# mesh_node.net
KiCad netlist of a schematic drawn in Altium Designer
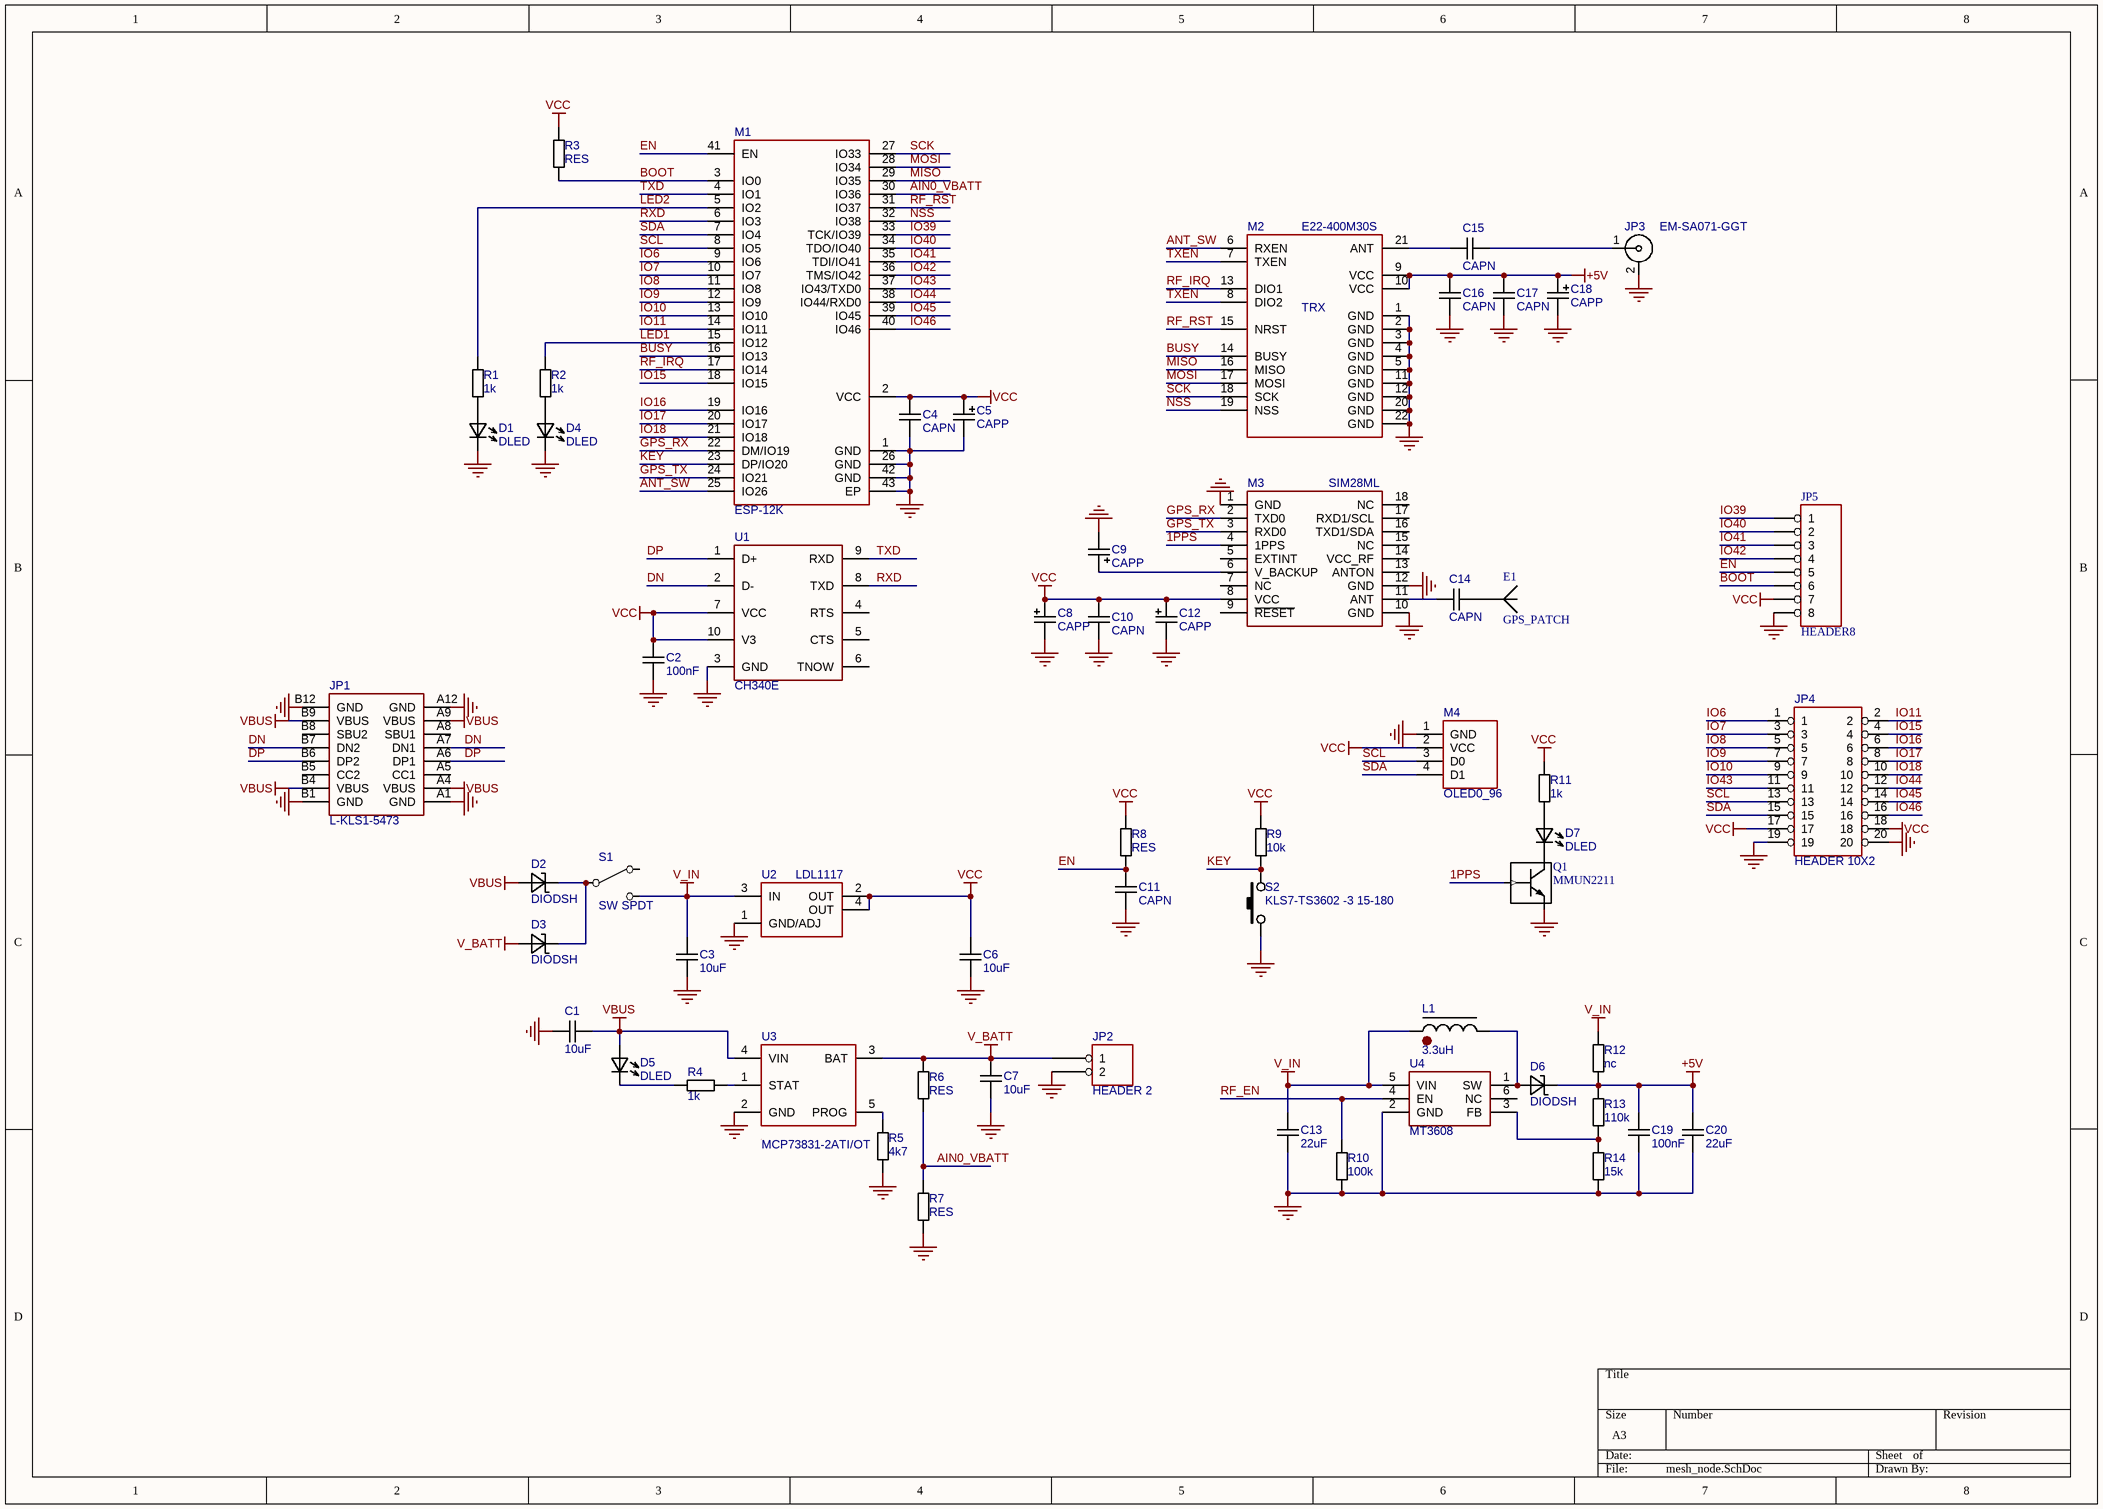
[diagram p0: mesh_node.SchDoc]

(export (version "E")
  (design (tool "Eeschema 10.0.6"))
  (components
    (comp (ref "C1")
      (value "10uF")
      (footprint "C-0805")
      (fields (field (name "VOLTAGE") "50V"))
      (libsource (lib "Passive") (part "CAPN"))
    )
    (comp (ref "C2")
      (value "100nF")
      (footprint "C-0603")
      (fields (field (name "VOLTAGE") "50V"))
      (libsource (lib "Passive") (part "CAPN"))
    )
    (comp (ref "C3")
      (value "10uF")
      (footprint "C-0805")
      (fields (field (name "VOLTAGE") "50V"))
      (libsource (lib "Passive") (part "CAPN"))
    )
    (comp (ref "C4")
      (value "CAPN")
      (footprint "C-0603")
      (fields (field (name "VOLTAGE") "50V"))
      (libsource (lib "Passive") (part "CAPN"))
    )
    (comp (ref "C5")
      (value "CAPP")
      (footprint "C_TANTAL_C")
      (fields (field (name "VOLTAGE") "16V"))
      (libsource (lib "Passive") (part "CAPP"))
    )
    (comp (ref "C6")
      (value "10uF")
      (footprint "C-0805")
      (fields (field (name "VOLTAGE") "50V"))
      (libsource (lib "Passive") (part "CAPN"))
    )
    (comp (ref "C7")
      (value "10uF")
      (footprint "C-0805")
      (fields (field (name "VOLTAGE") "50V"))
      (libsource (lib "Passive") (part "CAPN"))
    )
    (comp (ref "C8")
      (value "CAPP")
      (footprint "C_TANTAL_C")
      (fields (field (name "VOLTAGE") "16V"))
      (libsource (lib "Passive") (part "CAPP"))
    )
    (comp (ref "C9")
      (value "CAPP")
      (footprint "C_TANTAL_C")
      (fields (field (name "VOLTAGE") "16V"))
      (libsource (lib "Passive") (part "CAPP"))
    )
    (comp (ref "C10")
      (value "CAPN")
      (footprint "C-0603")
      (fields (field (name "VOLTAGE") "50V"))
      (libsource (lib "Passive") (part "CAPN"))
    )
    (comp (ref "C11")
      (value "CAPN")
      (footprint "C-0603")
      (fields (field (name "VOLTAGE") "50V"))
      (libsource (lib "Passive") (part "CAPN"))
    )
    (comp (ref "C12")
      (value "CAPP")
      (footprint "C_TANTAL_C")
      (fields (field (name "VOLTAGE") "16V"))
      (libsource (lib "Passive") (part "CAPP"))
    )
    (comp (ref "C13")
      (value "22uF")
      (footprint "C-0805")
      (fields (field (name "VOLTAGE") "50V"))
      (libsource (lib "Passive") (part "CAPN"))
    )
    (comp (ref "C14")
      (value "CAPN")
      (footprint "C-0603")
      (fields (field (name "VOLTAGE") "50V"))
      (libsource (lib "Passive") (part "CAPN"))
    )
    (comp (ref "C15")
      (value "CAPN")
      (footprint "C-0603")
      (fields (field (name "VOLTAGE") "50V"))
      (libsource (lib "Passive") (part "CAPN"))
    )
    (comp (ref "C16")
      (value "CAPN")
      (footprint "C-0603")
      (fields (field (name "VOLTAGE") "50V"))
      (libsource (lib "Passive") (part "CAPN"))
    )
    (comp (ref "C17")
      (value "CAPN")
      (footprint "C-0603")
      (fields (field (name "VOLTAGE") "50V"))
      (libsource (lib "Passive") (part "CAPN"))
    )
    (comp (ref "C18")
      (value "CAPP")
      (footprint "C_TANTAL_C")
      (fields (field (name "VOLTAGE") "16V"))
      (libsource (lib "Passive") (part "CAPP"))
    )
    (comp (ref "C19")
      (value "100nF")
      (footprint "C-0603")
      (fields (field (name "VOLTAGE") "50V"))
      (libsource (lib "Passive") (part "CAPN"))
    )
    (comp (ref "C20")
      (value "22uF")
      (footprint "C-0805")
      (fields (field (name "VOLTAGE") "50V"))
      (libsource (lib "Passive") (part "CAPN"))
    )
    (comp (ref "D1") (value "DLED") (footprint "LED_3mm_RED") (libsource (lib "Diodes") (part "DLED")))
    (comp (ref "D2") (value "DIODSH") (footprint "D-SMA") (libsource (lib "Diodes") (part "DIODSH")))
    (comp (ref "D3") (value "DIODSH") (footprint "D-SMA") (libsource (lib "Diodes") (part "DIODSH")))
    (comp (ref "D4") (value "DLED") (footprint "LED_3mm_RED") (libsource (lib "Diodes") (part "DLED")))
    (comp (ref "D5") (value "DLED") (footprint "LED_3mm_RED") (libsource (lib "Diodes") (part "DLED")))
    (comp (ref "D6") (value "DIODSH") (footprint "D_SMA_NUM") (libsource (lib "Diodes") (part "DIODSH")))
    (comp (ref "D7") (value "DLED") (footprint "LED_3mm_RED") (libsource (lib "Diodes") (part "DLED")))
    (comp (ref "E1")
      (value "GPS_PATCH")
      (footprint "GPSANT_1818")
      (libsource (lib "Connectors") (part "ANT"))
    )
    (comp (ref "JP1")
      (value "L-KLS1-5473")
      (footprint "USB_C_SMD_SLOT")
      (libsource (lib "Connectors") (part "L-KLS1-5473"))
    )
    (comp (ref "JP2")
      (value "HEADER 2")
      (footprint "PLS1-2")
      (libsource (lib "Connectors") (part "HEADER 2"))
    )
    (comp (ref "JP3")
      (value "EM-SA071-GGT")
      (footprint "SMA_F_EDGE")
      (description "SMA Female R/A PCB Mount")
      (libsource (lib "Connectors") (part "SMA"))
    )
    (comp (ref "JP4")
      (value "HEADER 10X2")
      (footprint "PLS2_10")
      (libsource (lib "Connectors") (part "HEADER 10X2"))
    )
    (comp (ref "JP5") (value "HEADER8") (footprint "PLS1-8") (libsource (lib "Connectors") (part "HEADER8")))
    (comp (ref "L1") (value "3.3uH") (footprint "CDRH6D38") (libsource (lib "Passive") (part "L*")))
    (comp (ref "M1") (value "ESP-12K") (footprint "ESP-12K") (libsource (lib "RFmodules") (part "ESP-12K")))
    (comp (ref "M2")
      (value "E22-400M30S")
      (footprint "PE22(400M30S)")
      (libsource (lib "RFmodules") (part "E22"))
    )
    (comp (ref "M3")
      (value "SIM28ML")
      (footprint "LGA18_GNSS")
      (libsource (lib "RFmodules") (part "SIM28ML"))
    )
    (comp (ref "M4")
      (value "OLED0_96")
      (footprint "OLED096_I2C")
      (libsource (lib "RFmodules") (part "OLED0_96_I2C"))
    )
    (comp (ref "Q1")
      (value "MMUN2211")
      (footprint "SOT-23")
      (libsource (lib "Transistors") (part "MMUN2211"))
    )
    (comp (ref "R1") (value "1k") (footprint "R-0603") (libsource (lib "Passive") (part "RES")))
    (comp (ref "R2") (value "1k") (footprint "R-0603") (libsource (lib "Passive") (part "RES")))
    (comp (ref "R3") (value "RES") (footprint "R-0603") (libsource (lib "Passive") (part "RES")))
    (comp (ref "R4") (value "1k") (footprint "R-0603") (libsource (lib "") (part "RES_2")))
    (comp (ref "R5") (value "4k7") (footprint "R-0603") (libsource (lib "Passive") (part "RES")))
    (comp (ref "R6") (value "RES") (footprint "R-0603") (libsource (lib "Passive") (part "RES")))
    (comp (ref "R7") (value "RES") (footprint "R-0603") (libsource (lib "Passive") (part "RES")))
    (comp (ref "R8") (value "RES") (footprint "R-0603") (libsource (lib "Passive") (part "RES")))
    (comp (ref "R9") (value "10k") (footprint "R-0603") (libsource (lib "") (part "RES_1")))
    (comp (ref "R10") (value "100k") (footprint "R-0603") (libsource (lib "Passive") (part "RES")))
    (comp (ref "R11") (value "1k") (footprint "R-0603") (libsource (lib "Passive") (part "RES")))
    (comp (ref "R12") (value "nc") (footprint "R-1206") (libsource (lib "Passive") (part "RES")))
    (comp (ref "R13") (value "110k") (footprint "R-0603") (libsource (lib "Passive") (part "RES")))
    (comp (ref "R14") (value "15k") (footprint "R-0603") (libsource (lib "Passive") (part "RES")))
    (comp (ref "S1")
      (value "SW SPDT")
      (footprint "SK-12D07VG5")
      (libsource (lib "Switches") (part "SW SPDT"))
    )
    (comp (ref "S2")
      (value "KLS7-TS3602 -3 15-180")
      (footprint "KLS7-TS3602")
      (libsource (lib "Switches") (part "SW-1"))
    )
    (comp (ref "U1") (value "CH340E") (footprint "MSOP-10") (libsource (lib "ICs") (part "CH340E")))
    (comp (ref "U2")
      (value "LDL1117")
      (footprint "SOT223")
      (description "LOW CURRENT ADJUSTABLE  VOLTAGE REGULATOR")
      (libsource (lib "ICs") (part "LDL1117"))
    )
    (comp (ref "U3")
      (value "MCP73831-2ATI/OT")
      (footprint "SOT-23-5")
      (fields
        (field (name "LIBRARY PART") "IC`s.SchLib")
        (field (name "FOOTPRINT PART") "IC-package.PcbLib")
        (field (name "MANUFACTURER") "Texas Instruments")
      )
      (libsource (lib "ICs") (part "MCP73831-2ATI/OT"))
    )
    (comp (ref "U4") (value "MT3608") (footprint "SOT-23-6") (libsource (lib "Power") (part "MT3608")))
  )
  (nets
    (net (code "1") (name "+5V") (class "Default")
      (node (ref "C16") (pin "1") (pinfunction "1_1") (pintype "passive"))
      (node (ref "C17") (pin "1") (pinfunction "1_1") (pintype "passive"))
      (node (ref "C18") (pin "2") (pinfunction "2_2") (pintype "passive"))
      (node (ref "C19") (pin "1") (pinfunction "1_1") (pintype "passive"))
      (node (ref "C20") (pin "1") (pinfunction "1_1") (pintype "passive"))
      (node (ref "D6") (pin "2") (pinfunction "2_2") (pintype "passive"))
      (node (ref "M2") (pin "10") (pinfunction "VCC_10") (pintype "passive"))
      (node (ref "M2") (pin "9") (pinfunction "VCC_9") (pintype "passive"))
      (node (ref "R12") (pin "1") (pinfunction "1_1") (pintype "passive"))
      (node (ref "R13") (pin "2") (pinfunction "2_2") (pintype "passive"))
    )
    (net (code "2") (name "/1PPS") (class "Default")
      (node (ref "M3") (pin "4") (pinfunction "1PPS_4") (pintype "passive"))
      (node (ref "Q1") (pin "1") (pinfunction "BASE_1") (pintype "input"))
    )
    (net (code "3") (name "/AIN0_VBATT") (class "Default")
      (node (ref "M1") (pin "30") (pinfunction "IO36_30") (pintype "passive"))
      (node (ref "R6") (pin "1") (pinfunction "1_1") (pintype "passive"))
      (node (ref "R7") (pin "2") (pinfunction "2_2") (pintype "passive"))
    )
    (net (code "4") (name "/ANT_SW") (class "Default")
      (node (ref "M1") (pin "25") (pinfunction "IO26_25") (pintype "passive"))
      (node (ref "M2") (pin "6") (pinfunction "RXEN_6") (pintype "passive"))
    )
    (net (code "5") (name "/BOOT") (class "Default")
      (node (ref "JP5") (pin "6") (pinfunction "6_6") (pintype "passive"))
      (node (ref "M1") (pin "3") (pinfunction "IO0_3") (pintype "passive"))
      (node (ref "R3") (pin "1") (pinfunction "1_1") (pintype "passive"))
    )
    (net (code "6") (name "/BUSY") (class "Default")
      (node (ref "M1") (pin "16") (pinfunction "IO13_16") (pintype "passive"))
      (node (ref "M2") (pin "14") (pinfunction "BUSY_14") (pintype "passive"))
    )
    (net (code "7") (name "/DN") (class "Default")
      (node (ref "JP1") (pin "A7") (pinfunction "DN1_A7") (pintype "passive"))
      (node (ref "JP1") (pin "B7") (pinfunction "DN2_B7") (pintype "passive"))
      (node (ref "U1") (pin "2") (pinfunction "D-_2") (pintype "passive"))
    )
    (net (code "8") (name "/DP") (class "Default")
      (node (ref "JP1") (pin "A6") (pinfunction "DP1_A6") (pintype "passive"))
      (node (ref "JP1") (pin "B6") (pinfunction "DP2_B6") (pintype "passive"))
      (node (ref "U1") (pin "1") (pinfunction "D+_1") (pintype "passive"))
    )
    (net (code "9") (name "/EN") (class "Default")
      (node (ref "C11") (pin "1") (pinfunction "1_1") (pintype "passive"))
      (node (ref "JP5") (pin "5") (pinfunction "5_5") (pintype "passive"))
      (node (ref "M1") (pin "41") (pinfunction "EN_41") (pintype "passive"))
      (node (ref "R8") (pin "1") (pinfunction "1_1") (pintype "passive"))
    )
    (net (code "10") (name "/GPS_RX") (class "Default")
      (node (ref "M1") (pin "22") (pinfunction "DM/IO19_22") (pintype "passive"))
      (node (ref "M3") (pin "2") (pinfunction "TXD0_2") (pintype "passive"))
    )
    (net (code "11") (name "/GPS_TX") (class "Default")
      (node (ref "M1") (pin "24") (pinfunction "IO21_24") (pintype "passive"))
      (node (ref "M3") (pin "3") (pinfunction "RXD0_3") (pintype "passive"))
    )
    (net (code "12") (name "/IO6") (class "Default")
      (node (ref "JP4") (pin "1") (pinfunction "1_1") (pintype "passive"))
      (node (ref "M1") (pin "9") (pinfunction "IO6_9") (pintype "passive"))
    )
    (net (code "13") (name "/IO7") (class "Default")
      (node (ref "JP4") (pin "3") (pinfunction "3_3") (pintype "passive"))
      (node (ref "M1") (pin "10") (pinfunction "IO7_10") (pintype "passive"))
    )
    (net (code "14") (name "/IO8") (class "Default")
      (node (ref "JP4") (pin "5") (pinfunction "5_5") (pintype "passive"))
      (node (ref "M1") (pin "11") (pinfunction "IO8_11") (pintype "passive"))
    )
    (net (code "15") (name "/IO9") (class "Default")
      (node (ref "JP4") (pin "7") (pinfunction "7_7") (pintype "passive"))
      (node (ref "M1") (pin "12") (pinfunction "IO9_12") (pintype "passive"))
    )
    (net (code "16") (name "/IO10") (class "Default")
      (node (ref "JP4") (pin "9") (pinfunction "9_9") (pintype "passive"))
      (node (ref "M1") (pin "13") (pinfunction "IO10_13") (pintype "passive"))
    )
    (net (code "17") (name "/IO11") (class "Default")
      (node (ref "JP4") (pin "2") (pinfunction "2_2") (pintype "passive"))
      (node (ref "M1") (pin "14") (pinfunction "IO11_14") (pintype "passive"))
    )
    (net (code "18") (name "/IO15") (class "Default")
      (node (ref "JP4") (pin "4") (pinfunction "4_4") (pintype "passive"))
      (node (ref "M1") (pin "18") (pinfunction "IO15_18") (pintype "passive"))
    )
    (net (code "19") (name "/IO16") (class "Default")
      (node (ref "JP4") (pin "6") (pinfunction "6_6") (pintype "passive"))
      (node (ref "M1") (pin "19") (pinfunction "IO16_19") (pintype "passive"))
    )
    (net (code "20") (name "/IO17") (class "Default")
      (node (ref "JP4") (pin "8") (pinfunction "8_8") (pintype "passive"))
      (node (ref "M1") (pin "20") (pinfunction "IO17_20") (pintype "passive"))
    )
    (net (code "21") (name "/IO18") (class "Default")
      (node (ref "JP4") (pin "10") (pinfunction "10_10") (pintype "passive"))
      (node (ref "M1") (pin "21") (pinfunction "IO18_21") (pintype "passive"))
    )
    (net (code "22") (name "/IO39") (class "Default")
      (node (ref "JP5") (pin "1") (pinfunction "1_1") (pintype "passive"))
      (node (ref "M1") (pin "33") (pinfunction "TCK/IO39_33") (pintype "passive"))
    )
    (net (code "23") (name "/IO40") (class "Default")
      (node (ref "JP5") (pin "2") (pinfunction "2_2") (pintype "passive"))
      (node (ref "M1") (pin "34") (pinfunction "TDO/IO40_34") (pintype "passive"))
    )
    (net (code "24") (name "/IO41") (class "Default")
      (node (ref "JP5") (pin "3") (pinfunction "3_3") (pintype "passive"))
      (node (ref "M1") (pin "35") (pinfunction "TDI/IO41_35") (pintype "passive"))
    )
    (net (code "25") (name "/IO42") (class "Default")
      (node (ref "JP5") (pin "4") (pinfunction "4_4") (pintype "passive"))
      (node (ref "M1") (pin "36") (pinfunction "TMS/IO42_36") (pintype "passive"))
    )
    (net (code "26") (name "/IO43") (class "Default")
      (node (ref "JP4") (pin "11") (pinfunction "11_11") (pintype "passive"))
      (node (ref "M1") (pin "37") (pinfunction "IO43/TXD0_37") (pintype "passive"))
    )
    (net (code "27") (name "/IO44") (class "Default")
      (node (ref "JP4") (pin "12") (pinfunction "12_12") (pintype "passive"))
      (node (ref "M1") (pin "38") (pinfunction "IO44/RXD0_38") (pintype "passive"))
    )
    (net (code "28") (name "/IO45") (class "Default")
      (node (ref "JP4") (pin "14") (pinfunction "14_14") (pintype "passive"))
      (node (ref "M1") (pin "39") (pinfunction "IO45_39") (pintype "passive"))
    )
    (net (code "29") (name "/IO46") (class "Default")
      (node (ref "JP4") (pin "16") (pinfunction "16_16") (pintype "passive"))
      (node (ref "M1") (pin "40") (pinfunction "IO46_40") (pintype "passive"))
    )
    (net (code "30") (name "/KEY") (class "Default")
      (node (ref "M1") (pin "23") (pinfunction "DP/IO20_23") (pintype "passive"))
      (node (ref "R9") (pin "2") (pinfunction "2_2") (pintype "passive"))
      (node (ref "S2") (pin "2") (pinfunction "2_2") (pintype "passive"))
    )
    (net (code "31") (name "/LED1") (class "Default")
      (node (ref "M1") (pin "15") (pinfunction "IO12_15") (pintype "passive"))
      (node (ref "R2") (pin "2") (pinfunction "2_2") (pintype "passive"))
    )
    (net (code "32") (name "/LED2") (class "Default")
      (node (ref "M1") (pin "5") (pinfunction "IO2_5") (pintype "passive"))
      (node (ref "R1") (pin "2") (pinfunction "2_2") (pintype "passive"))
    )
    (net (code "33") (name "/MISO") (class "Default")
      (node (ref "M1") (pin "29") (pinfunction "IO35_29") (pintype "passive"))
      (node (ref "M2") (pin "16") (pinfunction "MISO_16") (pintype "passive"))
    )
    (net (code "34") (name "/MOSI") (class "Default")
      (node (ref "M1") (pin "28") (pinfunction "IO34_28") (pintype "passive"))
      (node (ref "M2") (pin "17") (pinfunction "MOSI_17") (pintype "passive"))
    )
    (net (code "35") (name "/NSS") (class "Default")
      (node (ref "M1") (pin "32") (pinfunction "IO38_32") (pintype "passive"))
      (node (ref "M2") (pin "19") (pinfunction "NSS_19") (pintype "passive"))
    )
    (net (code "36") (name "/RF_EN") (class "Default")
      (node (ref "R10") (pin "2") (pinfunction "2_2") (pintype "passive"))
      (node (ref "U4") (pin "4") (pinfunction "EN_4") (pintype "passive"))
    )
    (net (code "37") (name "/RF_IRQ") (class "Default")
      (node (ref "M1") (pin "17") (pinfunction "IO14_17") (pintype "passive"))
      (node (ref "M2") (pin "13") (pinfunction "DIO1_13") (pintype "passive"))
    )
    (net (code "38") (name "/RF_RST") (class "Default")
      (node (ref "M1") (pin "31") (pinfunction "IO37_31") (pintype "passive"))
      (node (ref "M2") (pin "15") (pinfunction "NRST_15") (pintype "passive"))
    )
    (net (code "39") (name "/RXD") (class "Default")
      (node (ref "M1") (pin "6") (pinfunction "IO3_6") (pintype "passive"))
      (node (ref "U1") (pin "8") (pinfunction "TXD_8") (pintype "passive"))
    )
    (net (code "40") (name "/SCK") (class "Default")
      (node (ref "M1") (pin "27") (pinfunction "IO33_27") (pintype "passive"))
      (node (ref "M2") (pin "18") (pinfunction "SCK_18") (pintype "passive"))
    )
    (net (code "41") (name "/SCL") (class "Default")
      (node (ref "JP4") (pin "13") (pinfunction "13_13") (pintype "passive"))
      (node (ref "M1") (pin "8") (pinfunction "IO5_8") (pintype "passive"))
      (node (ref "M4") (pin "3") (pinfunction "D0_3") (pintype "passive"))
    )
    (net (code "42") (name "/SDA") (class "Default")
      (node (ref "JP4") (pin "15") (pinfunction "15_15") (pintype "passive"))
      (node (ref "M1") (pin "7") (pinfunction "IO4_7") (pintype "passive"))
      (node (ref "M4") (pin "4") (pinfunction "D1_4") (pintype "passive"))
    )
    (net (code "43") (name "/TXD") (class "Default")
      (node (ref "M1") (pin "4") (pinfunction "IO1_4") (pintype "passive"))
      (node (ref "U1") (pin "9") (pinfunction "RXD_9") (pintype "passive"))
    )
    (net (code "44") (name "/TXEN") (class "Default")
      (node (ref "M2") (pin "7") (pinfunction "TXEN_7") (pintype "passive"))
      (node (ref "M2") (pin "8") (pinfunction "DIO2_8") (pintype "passive"))
    )
    (net (code "45") (name "GND") (class "Default")
      (node (ref "C1") (pin "1") (pinfunction "1_1") (pintype "passive"))
      (node (ref "C10") (pin "2") (pinfunction "2_2") (pintype "passive"))
      (node (ref "C11") (pin "2") (pinfunction "2_2") (pintype "passive"))
      (node (ref "C12") (pin "1") (pinfunction "1_1") (pintype "passive"))
      (node (ref "C13") (pin "2") (pinfunction "2_2") (pintype "passive"))
      (node (ref "C16") (pin "2") (pinfunction "2_2") (pintype "passive"))
      (node (ref "C17") (pin "2") (pinfunction "2_2") (pintype "passive"))
      (node (ref "C18") (pin "1") (pinfunction "1_1") (pintype "passive"))
      (node (ref "C19") (pin "2") (pinfunction "2_2") (pintype "passive"))
      (node (ref "C2") (pin "1") (pinfunction "1_1") (pintype "passive"))
      (node (ref "C20") (pin "2") (pinfunction "2_2") (pintype "passive"))
      (node (ref "C3") (pin "2") (pinfunction "2_2") (pintype "passive"))
      (node (ref "C4") (pin "2") (pinfunction "2_2") (pintype "passive"))
      (node (ref "C5") (pin "1") (pinfunction "1_1") (pintype "passive"))
      (node (ref "C6") (pin "2") (pinfunction "2_2") (pintype "passive"))
      (node (ref "C7") (pin "1") (pinfunction "1_1") (pintype "passive"))
      (node (ref "C8") (pin "1") (pinfunction "1_1") (pintype "passive"))
      (node (ref "C9") (pin "1") (pinfunction "1_1") (pintype "passive"))
      (node (ref "D1") (pin "2") (pinfunction "2_2") (pintype "passive"))
      (node (ref "D4") (pin "2") (pinfunction "2_2") (pintype "passive"))
      (node (ref "JP1") (pin "A1") (pinfunction "GND_A1") (pintype "passive"))
      (node (ref "JP1") (pin "A12") (pinfunction "GND_A12") (pintype "passive"))
      (node (ref "JP1") (pin "B1") (pinfunction "GND_B1") (pintype "passive"))
      (node (ref "JP1") (pin "B12") (pinfunction "GND_B12") (pintype "passive"))
      (node (ref "JP2") (pin "2") (pinfunction "2_2") (pintype "passive"))
      (node (ref "JP3") (pin "2") (pinfunction "2_2") (pintype "passive"))
      (node (ref "JP4") (pin "19") (pinfunction "19_19") (pintype "passive"))
      (node (ref "JP4") (pin "20") (pinfunction "20_20") (pintype "passive"))
      (node (ref "JP5") (pin "8") (pinfunction "8_8") (pintype "passive"))
      (node (ref "M1") (pin "1") (pinfunction "GND_1") (pintype "passive"))
      (node (ref "M1") (pin "26") (pinfunction "GND_26") (pintype "passive"))
      (node (ref "M1") (pin "42") (pinfunction "GND_42") (pintype "passive"))
      (node (ref "M1") (pin "43") (pinfunction "EP_43") (pintype "passive"))
      (node (ref "M2") (pin "1") (pinfunction "GND_1") (pintype "passive"))
      (node (ref "M2") (pin "11") (pinfunction "GND_11") (pintype "passive"))
      (node (ref "M2") (pin "12") (pinfunction "GND_12") (pintype "passive"))
      (node (ref "M2") (pin "2") (pinfunction "GND_2") (pintype "passive"))
      (node (ref "M2") (pin "20") (pinfunction "GND_20") (pintype "passive"))
      (node (ref "M2") (pin "22") (pinfunction "GND_22") (pintype "passive"))
      (node (ref "M2") (pin "3") (pinfunction "GND_3") (pintype "passive"))
      (node (ref "M2") (pin "4") (pinfunction "GND_4") (pintype "passive"))
      (node (ref "M2") (pin "5") (pinfunction "GND_5") (pintype "passive"))
      (node (ref "M3") (pin "1") (pinfunction "GND_1") (pintype "passive"))
      (node (ref "M3") (pin "10") (pinfunction "GND_10") (pintype "passive"))
      (node (ref "M3") (pin "12") (pinfunction "GND_12") (pintype "passive"))
      (node (ref "M4") (pin "1") (pinfunction "GND_1") (pintype "passive"))
      (node (ref "Q1") (pin "2") (pinfunction "EMITTER_2") (pintype "passive"))
      (node (ref "R10") (pin "1") (pinfunction "1_1") (pintype "passive"))
      (node (ref "R14") (pin "1") (pinfunction "1_1") (pintype "passive"))
      (node (ref "R5") (pin "1") (pinfunction "1_1") (pintype "passive"))
      (node (ref "R7") (pin "1") (pinfunction "1_1") (pintype "passive"))
      (node (ref "S2") (pin "1") (pinfunction "1_1") (pintype "passive"))
      (node (ref "U1") (pin "3") (pinfunction "GND_3") (pintype "passive"))
      (node (ref "U2") (pin "1") (pinfunction "GND/ADJ_1") (pintype "power_in"))
      (node (ref "U3") (pin "2") (pinfunction "GND_2") (pintype "passive"))
      (node (ref "U4") (pin "2") (pinfunction "GND_2") (pintype "passive"))
    )
    (net (code "46") (name "Net-(C14-Pad2)") (class "Default")
      (node (ref "C14") (pin "2") (pinfunction "2_2") (pintype "passive"))
      (node (ref "E1") (pin "1") (pinfunction "1_1") (pintype "passive"))
    )
    (net (code "47") (name "Net-(C15-Pad2)") (class "Default")
      (node (ref "C15") (pin "2") (pinfunction "2_2") (pintype "passive"))
      (node (ref "JP3") (pin "1") (pinfunction "1_1") (pintype "passive"))
    )
    (net (code "48") (name "Net-(D1-Pad1)") (class "Default")
      (node (ref "D1") (pin "1") (pinfunction "1_1") (pintype "passive"))
      (node (ref "R1") (pin "1") (pinfunction "1_1") (pintype "passive"))
    )
    (net (code "49") (name "Net-(D4-Pad1)") (class "Default")
      (node (ref "D4") (pin "1") (pinfunction "1_1") (pintype "passive"))
      (node (ref "R2") (pin "1") (pinfunction "1_1") (pintype "passive"))
    )
    (net (code "50") (name "Net-(D5-Pad2)") (class "Default")
      (node (ref "D5") (pin "2") (pinfunction "2_2") (pintype "passive"))
      (node (ref "R4") (pin "2") (pinfunction "2_2") (pintype "passive"))
    )
    (net (code "51") (name "Net-(D7-Pad1)") (class "Default")
      (node (ref "D7") (pin "1") (pinfunction "1_1") (pintype "passive"))
      (node (ref "R11") (pin "1") (pinfunction "1_1") (pintype "passive"))
    )
    (net (code "52") (name "Net-(M2-ANT)") (class "Default")
      (node (ref "C15") (pin "1") (pinfunction "1_1") (pintype "passive"))
      (node (ref "M2") (pin "21") (pinfunction "ANT_21") (pintype "passive"))
    )
    (net (code "53") (name "Net-(M3-ANT)") (class "Default")
      (node (ref "C14") (pin "1") (pinfunction "1_1") (pintype "passive"))
      (node (ref "M3") (pin "11") (pinfunction "ANT_11") (pintype "passive"))
    )
    (net (code "54") (name "Net-(M3-V_BACKUP)") (class "Default")
      (node (ref "C9") (pin "2") (pinfunction "2_2") (pintype "passive"))
      (node (ref "M3") (pin "6") (pinfunction "V_BACKUP_6") (pintype "passive"))
    )
    (net (code "55") (name "Net-(Q1-COLLECTOR)") (class "Default")
      (node (ref "D7") (pin "2") (pinfunction "2_2") (pintype "passive"))
      (node (ref "Q1") (pin "3") (pinfunction "COLLECTOR_3") (pintype "passive"))
    )
    (net (code "56") (name "Net-(S1-COMMON)") (class "Default")
      (node (ref "D2") (pin "2") (pinfunction "2_2") (pintype "passive"))
      (node (ref "D3") (pin "2") (pinfunction "2_2") (pintype "passive"))
      (node (ref "S1") (pin "2") (pinfunction "COMMON_2") (pintype "passive"))
    )
    (net (code "57") (name "Net-(U3-PROG)") (class "Default")
      (node (ref "R5") (pin "2") (pinfunction "2_2") (pintype "passive"))
      (node (ref "U3") (pin "5") (pinfunction "PROG_5") (pintype "passive"))
    )
    (net (code "58") (name "Net-(U3-STAT)") (class "Default")
      (node (ref "R4") (pin "1") (pinfunction "1_1") (pintype "passive"))
      (node (ref "U3") (pin "1") (pinfunction "STAT_1") (pintype "passive"))
    )
    (net (code "59") (name "Net-(U4-FB)") (class "Default")
      (node (ref "R13") (pin "1") (pinfunction "1_1") (pintype "passive"))
      (node (ref "R14") (pin "2") (pinfunction "2_2") (pintype "passive"))
      (node (ref "U4") (pin "3") (pinfunction "FB_3") (pintype "passive"))
    )
    (net (code "60") (name "Net-(U4-SW)") (class "Default")
      (node (ref "D6") (pin "1") (pinfunction "1_1") (pintype "passive"))
      (node (ref "L1") (pin "2") (pinfunction "2_2") (pintype "passive"))
      (node (ref "U4") (pin "1") (pinfunction "SW_1") (pintype "passive"))
    )
    (net (code "61") (name "VBUS") (class "Default")
      (node (ref "C1") (pin "2") (pinfunction "2_2") (pintype "passive"))
      (node (ref "D2") (pin "1") (pinfunction "1_1") (pintype "passive"))
      (node (ref "D5") (pin "1") (pinfunction "1_1") (pintype "passive"))
      (node (ref "JP1") (pin "A4") (pinfunction "VBUS_A4") (pintype "passive"))
      (node (ref "JP1") (pin "A9") (pinfunction "VBUS_A9") (pintype "passive"))
      (node (ref "JP1") (pin "B4") (pinfunction "VBUS_B4") (pintype "passive"))
      (node (ref "JP1") (pin "B9") (pinfunction "VBUS_B9") (pintype "passive"))
      (node (ref "U3") (pin "4") (pinfunction "VIN_4") (pintype "passive"))
    )
    (net (code "62") (name "VCC") (class "Default")
      (node (ref "C10") (pin "1") (pinfunction "1_1") (pintype "passive"))
      (node (ref "C12") (pin "2") (pinfunction "2_2") (pintype "passive"))
      (node (ref "C2") (pin "2") (pinfunction "2_2") (pintype "passive"))
      (node (ref "C4") (pin "1") (pinfunction "1_1") (pintype "passive"))
      (node (ref "C5") (pin "2") (pinfunction "2_2") (pintype "passive"))
      (node (ref "C6") (pin "1") (pinfunction "1_1") (pintype "passive"))
      (node (ref "C8") (pin "2") (pinfunction "2_2") (pintype "passive"))
      (node (ref "JP4") (pin "17") (pinfunction "17_17") (pintype "passive"))
      (node (ref "JP4") (pin "18") (pinfunction "18_18") (pintype "passive"))
      (node (ref "JP5") (pin "7") (pinfunction "7_7") (pintype "passive"))
      (node (ref "M1") (pin "2") (pinfunction "VCC_2") (pintype "passive"))
      (node (ref "M3") (pin "8") (pinfunction "VCC_8") (pintype "passive"))
      (node (ref "M4") (pin "2") (pinfunction "VCC_2") (pintype "passive"))
      (node (ref "R11") (pin "2") (pinfunction "2_2") (pintype "passive"))
      (node (ref "R3") (pin "2") (pinfunction "2_2") (pintype "passive"))
      (node (ref "R8") (pin "2") (pinfunction "2_2") (pintype "passive"))
      (node (ref "R9") (pin "1") (pinfunction "1_1") (pintype "passive"))
      (node (ref "U1") (pin "10") (pinfunction "V3_10") (pintype "passive"))
      (node (ref "U1") (pin "7") (pinfunction "VCC_7") (pintype "passive"))
      (node (ref "U2") (pin "2") (pinfunction "OUT_2") (pintype "power_in"))
      (node (ref "U2") (pin "4") (pinfunction "OUT_4") (pintype "power_in"))
    )
    (net (code "63") (name "VSS") (class "Default")
      (node (ref "JP1") (pin "17") (pinfunction "VSS_17") (pintype "power_in"))
    )
    (net (code "64") (name "V_BATT") (class "Default")
      (node (ref "C7") (pin "2") (pinfunction "2_2") (pintype "passive"))
      (node (ref "D3") (pin "1") (pinfunction "1_1") (pintype "passive"))
      (node (ref "JP2") (pin "1") (pinfunction "1_1") (pintype "passive"))
      (node (ref "R6") (pin "2") (pinfunction "2_2") (pintype "passive"))
      (node (ref "U3") (pin "3") (pinfunction "BAT_3") (pintype "passive"))
    )
    (net (code "65") (name "V_IN") (class "Default")
      (node (ref "C13") (pin "1") (pinfunction "1_1") (pintype "passive"))
      (node (ref "C3") (pin "1") (pinfunction "1_1") (pintype "passive"))
      (node (ref "L1") (pin "1") (pinfunction "1_1") (pintype "passive"))
      (node (ref "R12") (pin "2") (pinfunction "2_2") (pintype "passive"))
      (node (ref "S1") (pin "3") (pinfunction "NO_3") (pintype "passive"))
      (node (ref "U2") (pin "3") (pinfunction "IN_3") (pintype "power_in"))
      (node (ref "U4") (pin "5") (pinfunction "VIN_5") (pintype "passive"))
    )
    (net (code "66") (name "unconnected-(JP1-CC1-PadA5)") (class "Default")
      (node (ref "JP1") (pin "A5") (pinfunction "CC1_A5") (pintype "passive"))
    )
    (net (code "67") (name "unconnected-(JP1-CC2-PadB5)") (class "Default")
      (node (ref "JP1") (pin "B5") (pinfunction "CC2_B5") (pintype "passive"))
    )
    (net (code "68") (name "unconnected-(JP1-SBU1-PadA8)") (class "Default")
      (node (ref "JP1") (pin "A8") (pinfunction "SBU1_A8") (pintype "passive"))
    )
    (net (code "69") (name "unconnected-(JP1-SBU2-PadB8)") (class "Default")
      (node (ref "JP1") (pin "B8") (pinfunction "SBU2_B8") (pintype "passive"))
    )
    (net (code "70") (name "unconnected-(M3-ANTON-Pad13)") (class "Default")
      (node (ref "M3") (pin "13") (pinfunction "ANTON_13") (pintype "passive"))
    )
    (net (code "71") (name "unconnected-(M3-EXTINT-Pad5)") (class "Default")
      (node (ref "M3") (pin "5") (pinfunction "EXTINT_5") (pintype "passive"))
    )
    (net (code "72") (name "unconnected-(M3-NC-Pad7)") (class "Default")
      (node (ref "M3") (pin "7") (pinfunction "NC_7") (pintype "passive"))
    )
    (net (code "73") (name "unconnected-(M3-NC-Pad15)") (class "Default")
      (node (ref "M3") (pin "15") (pinfunction "NC_15") (pintype "passive"))
    )
    (net (code "74") (name "unconnected-(M3-NC-Pad18)") (class "Default")
      (node (ref "M3") (pin "18") (pinfunction "NC_18") (pintype "passive"))
    )
    (net (code "75") (name "unconnected-(M3-RXD1{slash}SCL-Pad17)") (class "Default")
      (node (ref "M3") (pin "17") (pinfunction "RXD1/SCL_17") (pintype "passive"))
    )
    (net (code "76") (name "unconnected-(M3-TXD1{slash}SDA-Pad16)") (class "Default")
      (node (ref "M3") (pin "16") (pinfunction "TXD1/SDA_16") (pintype "passive"))
    )
    (net (code "77") (name "unconnected-(M3-VCC_RF-Pad14)") (class "Default")
      (node (ref "M3") (pin "14") (pinfunction "VCC_RF_14") (pintype "passive"))
    )
    (net (code "78") (name "unconnected-(M3-~{RESET}-Pad9)") (class "Default")
      (node (ref "M3") (pin "9") (pinfunction "~{RESET}_9") (pintype "passive"))
    )
    (net (code "79") (name "unconnected-(S1-NC-Pad1)") (class "Default")
      (node (ref "S1") (pin "1") (pinfunction "NC_1") (pintype "passive"))
    )
    (net (code "80") (name "unconnected-(U1-CTS-Pad5)") (class "Default")
      (node (ref "U1") (pin "5") (pinfunction "CTS_5") (pintype "passive"))
    )
    (net (code "81") (name "unconnected-(U1-RTS-Pad4)") (class "Default")
      (node (ref "U1") (pin "4") (pinfunction "RTS_4") (pintype "passive"))
    )
    (net (code "82") (name "unconnected-(U1-TNOW-Pad6)") (class "Default")
      (node (ref "U1") (pin "6") (pinfunction "TNOW_6") (pintype "passive"))
    )
    (net (code "83") (name "unconnected-(U4-NC-Pad6)") (class "Default")
      (node (ref "U4") (pin "6") (pinfunction "NC_6") (pintype "passive"))
    )
  )
)
